# HBridge.net
KiCad netlist of a schematic drawn in Altium Designer
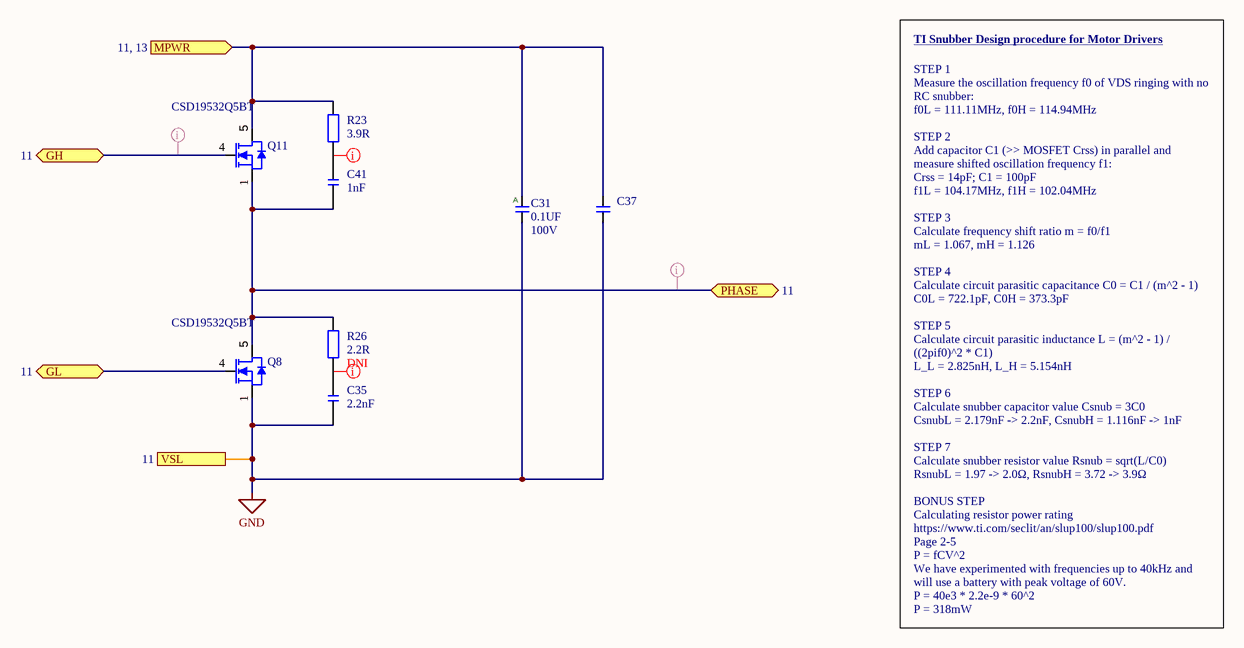
[diagram p0: HBridge.SchDoc]

(export (version "E")
  (design (tool "Eeschema 10.0.6"))
  (components
    (comp (ref "C31")
      (value "0.1UF")
      (footprint "C0603")
      (description "CAP, CER, X7S, 0.1uF, 100V, 10%, 0603, AUTOGRADE")
      (fields
        (field (name "MFG") "TDK")
        (field (name "VOLTAGE") "100V")
        (field (name "Comment") "__Template_Cap_Auto")
      )
      (libsource (lib "AltiumReleaseLibDB") (part "__Template_Cap_Auto"))
    )
    (comp (ref "C35")
      (value "2.2nF")
      (footprint "C0603")
      (description "Multilayer Ceramic Capacitors MLCC - SMD/SMT 0603 2.2nF 100volts X7R 10%")
      (fields (field (name "MFG") "Vishay / Vitramon") (field (name "VOLTAGE") "100V"))
      (libsource (lib "MiscSch1") (part "C"))
    )
    (comp (ref "C37")
      (value "4.7UF")
      (footprint "C1210")
      (description "CAP CER 4.7UF 100V X7S 1210")
      (fields (field (name "MFG") "Taiyo Yuden") (field (name "VOLTAGE") "100V"))
      (libsource (lib "capacitor") (part "CAP_CER_1210_4.7UF_100V_20%_X7S"))
    )
    (comp (ref "C41")
      (value "1nF")
      (footprint "C0603")
      (description "Multilayer Ceramic Capacitors MLCC - SMD/SMT 0603 1.0nF 100volts X7R 10%")
      (fields (field (name "MFG") "Vishay / Vitramon") (field (name "VOLTAGE") "100V"))
      (libsource (lib "MiscSch1") (part "C"))
    )
    (comp (ref "NT3")
      (value "Mechanical Feature NET_TIE_10MIL")
      (footprint "NETTIE_10MIL")
      (description "Net Tie, 10mil trace")
      (libsource (lib "Components") (part "NET_TIE"))
    )
    (comp (ref "Q8")
      (value "CSD19532Q5BT")
      (footprint "TI_SON5X6")
      (description "MOSFET N-CH 100V 100A 8SON")
      (fields (field (name "MFG") "Texas Instruments") (field (name "Comment") "TI CSD19532Q5B"))
      (libsource (lib "Components") (part "NFET_POWER33"))
    )
    (comp (ref "Q11")
      (value "CSD19532Q5BT")
      (footprint "TI_SON5X6")
      (description "MOSFET N-CH 100V 100A 8SON")
      (fields (field (name "MFG") "Texas Instruments") (field (name "Comment") "TI CSD19532Q5B"))
      (libsource (lib "Components") (part "NFET_POWER33"))
    )
    (comp (ref "R23")
      (value "3.9R")
      (footprint "R0805")
      (description "RES SMD 3.9 OHM 5% 1/2W 0805")
      (fields (field (name "MFG") "Panasonic Electronic Components"))
      (libsource (lib "MiscSch1") (part "R"))
    )
    (comp (ref "R26")
      (value "2.2R")
      (footprint "R0805")
      (description "RES SMD 2.2 OHM 1% 1/2W 0805")
      (fields (field (name "MFG") "Vishay Dale") (field (name "DNI") "DNI"))
      (libsource (lib "MiscSch1") (part "R"))
    )
  )
  (nets
    (net (code "1") (name "/GH") (class "Default")
      (node (ref "Q11") (pin "4") (pinfunction "G_4") (pintype "passive"))
    )
    (net (code "2") (name "/GL") (class "Default")
      (node (ref "Q8") (pin "4") (pinfunction "G_4") (pintype "passive"))
    )
    (net (code "3") (name "/MPWR") (class "Default")
      (node (ref "C31") (pin "1") (pintype "passive"))
      (node (ref "C37") (pin "1") (pintype "passive"))
      (node (ref "Q11") (pin "5") (pinfunction "D_5") (pintype "passive"))
      (node (ref "R23") (pin "2") (pinfunction "2_2") (pintype "passive"))
    )
    (net (code "4") (name "/PHASE") (class "Default")
      (node (ref "C41") (pin "1") (pinfunction "1_1") (pintype "passive"))
      (node (ref "Q11") (pin "1") (pinfunction "S_1") (pintype "passive"))
      (node (ref "Q8") (pin "5") (pinfunction "D_5") (pintype "passive"))
      (node (ref "R26") (pin "2") (pinfunction "2_2") (pintype "passive"))
    )
    (net (code "5") (name "/VSL") (class "Default")
      (node (ref "NT3") (pin "1") (pinfunction "1_1") (pintype "passive"))
    )
    (net (code "6") (name "GND") (class "Default")
      (node (ref "C31") (pin "2") (pintype "passive"))
      (node (ref "C35") (pin "1") (pinfunction "1_1") (pintype "passive"))
      (node (ref "C37") (pin "2") (pintype "passive"))
      (node (ref "NT3") (pin "2") (pinfunction "2_2") (pintype "passive"))
      (node (ref "Q8") (pin "1") (pinfunction "S_1") (pintype "passive"))
    )
    (net (code "7") (name "Net-(C35-Pad2)") (class "Default")
      (node (ref "C35") (pin "2") (pinfunction "2_2") (pintype "passive"))
      (node (ref "R26") (pin "1") (pinfunction "1_1") (pintype "passive"))
    )
    (net (code "8") (name "Net-(C41-Pad2)") (class "Default")
      (node (ref "C41") (pin "2") (pinfunction "2_2") (pintype "passive"))
      (node (ref "R23") (pin "1") (pinfunction "1_1") (pintype "passive"))
    )
  )
)
